# myRolloCtl.net
KiCad netlist of a schematic drawn in EAGLE
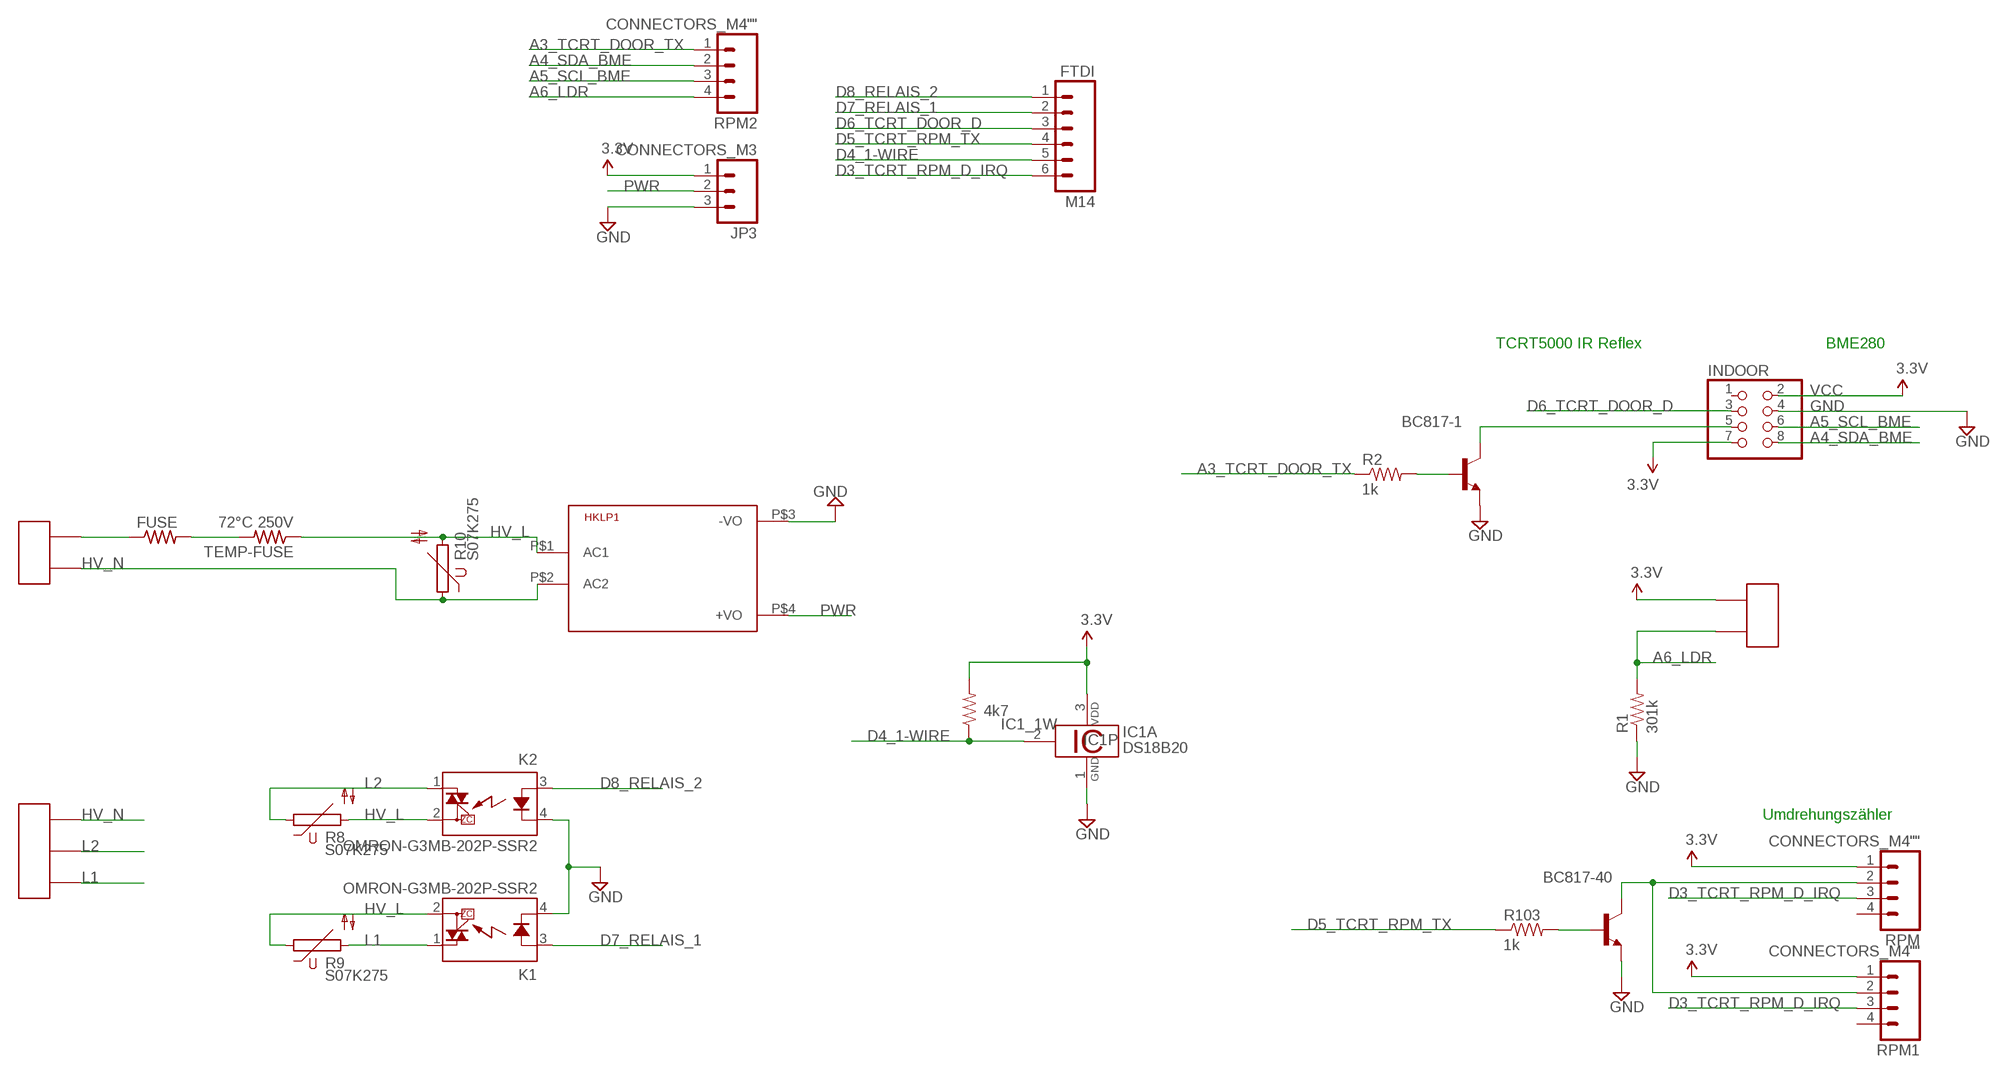
[diagram p0: schematic, sheet 1]

(export (version "E")
  (design (tool "Eeschema 10.0.6"))
  (components
    (comp (ref "BC817-1")
      (value "BC817-40-NPN-SOT23-BEC")
      (footprint "eagle-import:SOT23-BEC")
      (libsource (lib "eagle-import") (part "-NPN-SOT23-BECBC817-40"))
    )
    (comp (ref "BC817-40")
      (value "BC817-40-NPN-SOT23-BEC")
      (footprint "eagle-import:SOT23-BEC")
      (libsource (lib "eagle-import") (part "-NPN-SOT23-BECBC817-40"))
    )
    (comp (ref "FUSE")
      (value "R-US_0613/5V")
      (footprint "eagle-import:P0613V")
      (libsource (lib "eagle-import") (part "R-US_0613/5V"))
    )
    (comp (ref "HKLP1")
      (value "HKLPM01")
      (footprint "eagle-import:HKLPM01")
      (libsource (lib "eagle-import") (part "HKLPM01"))
    )
    (comp (ref "IC1")
      (value "DS18B20")
      (footprint "eagle-import:TO92-")
      (libsource (lib "eagle-import") (part "DS18B20"))
    )
    (comp (ref "INDOOR")
      (value "PINHD-2X4")
      (footprint "eagle-import:2X04")
      (libsource (lib "eagle-import") (part "PINHD-2X4"))
    )
    (comp (ref "JP3")
      (value "CONNECTORS_M3")
      (footprint "eagle-import:CONNECTORS_1X3")
      (libsource (lib "eagle-import") (part "CONNECTORS_M3"))
    )
    (comp (ref "K1")
      (value "OMRON-G3MB-202P-SSR2")
      (footprint "eagle-import:OMRON-G3MB-202P-SSR")
      (fields (field (name "MPN") "S202S02F"))
      (libsource (lib "eagle-import") (part "OMRON-G3MB-202P-SSR2"))
    )
    (comp (ref "K2")
      (value "OMRON-G3MB-202P-SSR2")
      (footprint "eagle-import:OMRON-G3MB-202P-SSR")
      (fields (field (name "MPN") "S202S02F"))
      (libsource (lib "eagle-import") (part "OMRON-G3MB-202P-SSR2"))
    )
    (comp (ref "M14")
      (value "FTDI")
      (footprint "eagle-import:1X06")
      (libsource (lib "eagle-import") (part "M06SIP"))
    )
    (comp (ref "R1")
      (value "301k")
      (footprint "eagle-import:0603-RES")
      (libsource (lib "eagle-import") (part "RESISTOR0603-RES"))
    )
    (comp (ref "R2")
      (value "1k")
      (footprint "eagle-import:0603-RES")
      (libsource (lib "eagle-import") (part "RESISTOR0603-RES"))
    )
    (comp (ref "R4")
      (value "4k7")
      (footprint "eagle-import:0603-RES")
      (libsource (lib "eagle-import") (part "RESISTOR0603-RES"))
    )
    (comp (ref "R8")
      (value "S07K275")
      (footprint "eagle-import:S07K275")
      (libsource (lib "eagle-import") (part "S07K275"))
    )
    (comp (ref "R9")
      (value "S07K275")
      (footprint "eagle-import:S07K275")
      (libsource (lib "eagle-import") (part "S07K275"))
    )
    (comp (ref "R10")
      (value "S07K275")
      (footprint "eagle-import:S07K275")
      (libsource (lib "eagle-import") (part "S07K275"))
    )
    (comp (ref "R103")
      (value "1k")
      (footprint "eagle-import:0603-RES")
      (libsource (lib "eagle-import") (part "RESISTOR0603-RES"))
    )
    (comp (ref "RPM")
      (value "CONNECTORS_M4\"\"")
      (footprint "eagle-import:CONNECTORS_1X4")
      (libsource (lib "eagle-import") (part "CONNECTORS_M4{dblquote}{dblquote}"))
    )
    (comp (ref "RPM1")
      (value "CONNECTORS_M4\"\"")
      (footprint "eagle-import:CONNECTORS_1X4")
      (libsource (lib "eagle-import") (part "CONNECTORS_M4{dblquote}{dblquote}"))
    )
    (comp (ref "RPM2")
      (value "CONNECTORS_M4\"\"")
      (footprint "eagle-import:CONNECTORS_1X4")
      (libsource (lib "eagle-import") (part "CONNECTORS_M4{dblquote}{dblquote}"))
    )
    (comp (ref "TEMP-FUSE")
      (value "72°C 250V")
      (footprint "eagle-import:0207_2V")
      (libsource (lib "eagle-import") (part "R-US_0207/2V"))
    )
    (comp (ref "U$2")
      (value "HDR_2PIN")
      (footprint "eagle-import:1X02_NS")
      (libsource (lib "eagle-import") (part "HDR_2PIN"))
    )
    (comp (ref "U$3")
      (value "HDR_3PIN")
      (footprint "eagle-import:1X03_LUMBERG-KRMC_3,5MM")
      (libsource (lib "eagle-import") (part "HDR_3PIN"))
    )
    (comp (ref "U$6")
      (value "HDR_2PIN1X02_3.5MM")
      (footprint "eagle-import:1X02_LUMBERG-KRMC_3,5MM")
      (libsource (lib "eagle-import") (part "HDR_2PIN1X02_3.5MM"))
    )
  )
  (nets
    (net (code "1") (name "/A3_TCRT_DOOR_TX") (class "Default")
      (node (ref "R2") (pin "1") (pinfunction "1_1") (pintype "passive"))
      (node (ref "RPM2") (pin "1") (pinfunction "1_1") (pintype "passive"))
    )
    (net (code "2") (name "/A4_SDA_BME") (class "Default")
      (node (ref "INDOOR") (pin "8") (pinfunction "8_8") (pintype "passive"))
      (node (ref "RPM2") (pin "2") (pinfunction "2_2") (pintype "passive"))
    )
    (net (code "3") (name "/A5_SCL_BME") (class "Default")
      (node (ref "INDOOR") (pin "6") (pinfunction "6_6") (pintype "passive"))
      (node (ref "RPM2") (pin "3") (pinfunction "3_3") (pintype "passive"))
    )
    (net (code "4") (name "/A6_LDR") (class "Default")
      (node (ref "R1") (pin "2") (pinfunction "2_2") (pintype "passive"))
      (node (ref "RPM2") (pin "4") (pinfunction "4_4") (pintype "passive"))
      (node (ref "U$2") (pin "2") (pinfunction "P$2_2") (pintype "bidirectional"))
    )
    (net (code "5") (name "/D3_TCRT_RPM_D_IRQ") (class "Default")
      (node (ref "M14") (pin "6") (pinfunction "6_6") (pintype "passive"))
      (node (ref "RPM") (pin "3") (pinfunction "3_3") (pintype "passive"))
      (node (ref "RPM1") (pin "3") (pinfunction "3_3") (pintype "passive"))
    )
    (net (code "6") (name "/D4_1-WIRE") (class "Default")
      (node (ref "IC1") (pin "2") (pinfunction "1W_2") (pintype "power_in"))
      (node (ref "M14") (pin "5") (pinfunction "5_5") (pintype "passive"))
      (node (ref "R4") (pin "1") (pinfunction "1_1") (pintype "passive"))
    )
    (net (code "7") (name "/D5_TCRT_RPM_TX") (class "Default")
      (node (ref "M14") (pin "4") (pinfunction "4_4") (pintype "passive"))
      (node (ref "R103") (pin "1") (pinfunction "1_1") (pintype "passive"))
    )
    (net (code "8") (name "/D6_TCRT_DOOR_D") (class "Default")
      (node (ref "INDOOR") (pin "3") (pinfunction "3_3") (pintype "passive"))
      (node (ref "M14") (pin "3") (pinfunction "3_3") (pintype "passive"))
    )
    (net (code "9") (name "/D7_RELAIS_1") (class "Default")
      (node (ref "K1") (pin "3") (pinfunction "A_3") (pintype "passive"))
      (node (ref "M14") (pin "2") (pinfunction "2_2") (pintype "passive"))
    )
    (net (code "10") (name "/D8_RELAIS_2") (class "Default")
      (node (ref "K2") (pin "3") (pinfunction "A_3") (pintype "passive"))
      (node (ref "M14") (pin "1") (pinfunction "1_1") (pintype "passive"))
    )
    (net (code "11") (name "/HV_L") (class "Default")
      (node (ref "HKLP1") (pin "P$1") (pinfunction "AC1_P$1") (pintype "bidirectional"))
      (node (ref "K1") (pin "2") (pinfunction "DS2_2") (pintype "passive"))
      (node (ref "K2") (pin "2") (pinfunction "DS2_2") (pintype "passive"))
      (node (ref "R10") (pin "2") (pinfunction "2_2") (pintype "passive"))
      (node (ref "R8") (pin "2") (pinfunction "2_2") (pintype "passive"))
      (node (ref "R9") (pin "1") (pinfunction "1_1") (pintype "passive"))
      (node (ref "TEMP-FUSE") (pin "1") (pinfunction "1_1") (pintype "passive"))
    )
    (net (code "12") (name "/HV_N") (class "Default")
      (node (ref "HKLP1") (pin "P$2") (pinfunction "AC2_P$2") (pintype "bidirectional"))
      (node (ref "R10") (pin "1") (pinfunction "1_1") (pintype "passive"))
      (node (ref "U$3") (pin "3") (pinfunction "P$3_3") (pintype "bidirectional"))
      (node (ref "U$6") (pin "1") (pinfunction "P$1_1") (pintype "bidirectional"))
    )
    (net (code "13") (name "/L1") (class "Default")
      (node (ref "K1") (pin "1") (pinfunction "DS1_1") (pintype "passive"))
      (node (ref "R9") (pin "2") (pinfunction "2_2") (pintype "passive"))
      (node (ref "U$3") (pin "1") (pinfunction "P$1_1") (pintype "bidirectional"))
    )
    (net (code "14") (name "/L2") (class "Default")
      (node (ref "K2") (pin "1") (pinfunction "DS1_1") (pintype "passive"))
      (node (ref "R8") (pin "1") (pinfunction "1_1") (pintype "passive"))
      (node (ref "U$3") (pin "2") (pinfunction "P$2_2") (pintype "bidirectional"))
    )
    (net (code "15") (name "/PWR") (class "Default")
      (node (ref "HKLP1") (pin "P$4") (pinfunction "+VO_P$4") (pintype "bidirectional"))
      (node (ref "JP3") (pin "2") (pinfunction "2_2") (pintype "passive"))
    )
    (net (code "16") (name "3.3V") (class "Default")
      (node (ref "IC1") (pin "3") (pinfunction "VDD_3") (pintype "power_in"))
      (node (ref "INDOOR") (pin "2") (pinfunction "2_2") (pintype "passive"))
      (node (ref "INDOOR") (pin "7") (pinfunction "7_7") (pintype "passive"))
      (node (ref "JP3") (pin "1") (pinfunction "1_1") (pintype "passive"))
      (node (ref "R4") (pin "2") (pinfunction "2_2") (pintype "passive"))
      (node (ref "RPM") (pin "1") (pinfunction "1_1") (pintype "passive"))
      (node (ref "RPM1") (pin "1") (pinfunction "1_1") (pintype "passive"))
      (node (ref "U$2") (pin "1") (pinfunction "P$1_1") (pintype "bidirectional"))
    )
    (net (code "17") (name "GND") (class "Default")
      (node (ref "BC817-1") (pin "E") (pinfunction "E_E") (pintype "passive"))
      (node (ref "BC817-40") (pin "E") (pinfunction "E_E") (pintype "passive"))
      (node (ref "HKLP1") (pin "P$3") (pinfunction "-VO_P$3") (pintype "bidirectional"))
      (node (ref "IC1") (pin "1") (pinfunction "GND_1") (pintype "power_in"))
      (node (ref "INDOOR") (pin "4") (pinfunction "4_4") (pintype "passive"))
      (node (ref "JP3") (pin "3") (pinfunction "3_3") (pintype "passive"))
      (node (ref "K1") (pin "4") (pinfunction "K_4") (pintype "passive"))
      (node (ref "K2") (pin "4") (pinfunction "K_4") (pintype "passive"))
      (node (ref "R1") (pin "1") (pinfunction "1_1") (pintype "passive"))
    )
    (net (code "18") (name "Net-(BC817-1-PadB)") (class "Default")
      (node (ref "BC817-1") (pin "B") (pinfunction "B_B") (pintype "passive"))
      (node (ref "R2") (pin "2") (pinfunction "2_2") (pintype "passive"))
    )
    (net (code "19") (name "Net-(BC817-1-PadC)") (class "Default")
      (node (ref "BC817-1") (pin "C") (pinfunction "C_C") (pintype "passive"))
      (node (ref "INDOOR") (pin "5") (pinfunction "5_5") (pintype "passive"))
    )
    (net (code "20") (name "Net-(BC817-40-PadB)") (class "Default")
      (node (ref "BC817-40") (pin "B") (pinfunction "B_B") (pintype "passive"))
      (node (ref "R103") (pin "2") (pinfunction "2_2") (pintype "passive"))
    )
    (net (code "21") (name "Net-(BC817-40-PadC)") (class "Default")
      (node (ref "BC817-40") (pin "C") (pinfunction "C_C") (pintype "passive"))
      (node (ref "RPM") (pin "2") (pinfunction "2_2") (pintype "passive"))
      (node (ref "RPM1") (pin "2") (pinfunction "2_2") (pintype "passive"))
    )
    (net (code "22") (name "Net-(FUSE-Pad2)") (class "Default")
      (node (ref "FUSE") (pin "2") (pinfunction "2_2") (pintype "passive"))
      (node (ref "TEMP-FUSE") (pin "2") (pinfunction "2_2") (pintype "passive"))
    )
    (net (code "23") (name "Net-(U$6-P$2)") (class "Default")
      (node (ref "FUSE") (pin "1") (pinfunction "1_1") (pintype "passive"))
      (node (ref "U$6") (pin "2") (pinfunction "P$2_2") (pintype "bidirectional"))
    )
    (net (code "24") (name "unconnected-(INDOOR-Pad1)") (class "Default")
      (node (ref "INDOOR") (pin "1") (pinfunction "1_1") (pintype "passive"))
    )
    (net (code "25") (name "unconnected-(RPM-Pad4)") (class "Default")
      (node (ref "RPM") (pin "4") (pinfunction "4_4") (pintype "passive"))
    )
    (net (code "26") (name "unconnected-(RPM1-Pad4)") (class "Default")
      (node (ref "RPM1") (pin "4") (pinfunction "4_4") (pintype "passive"))
    )
  )
)
